# expansion_module_microSD.net
KiCad netlist of a schematic drawn in EAGLE
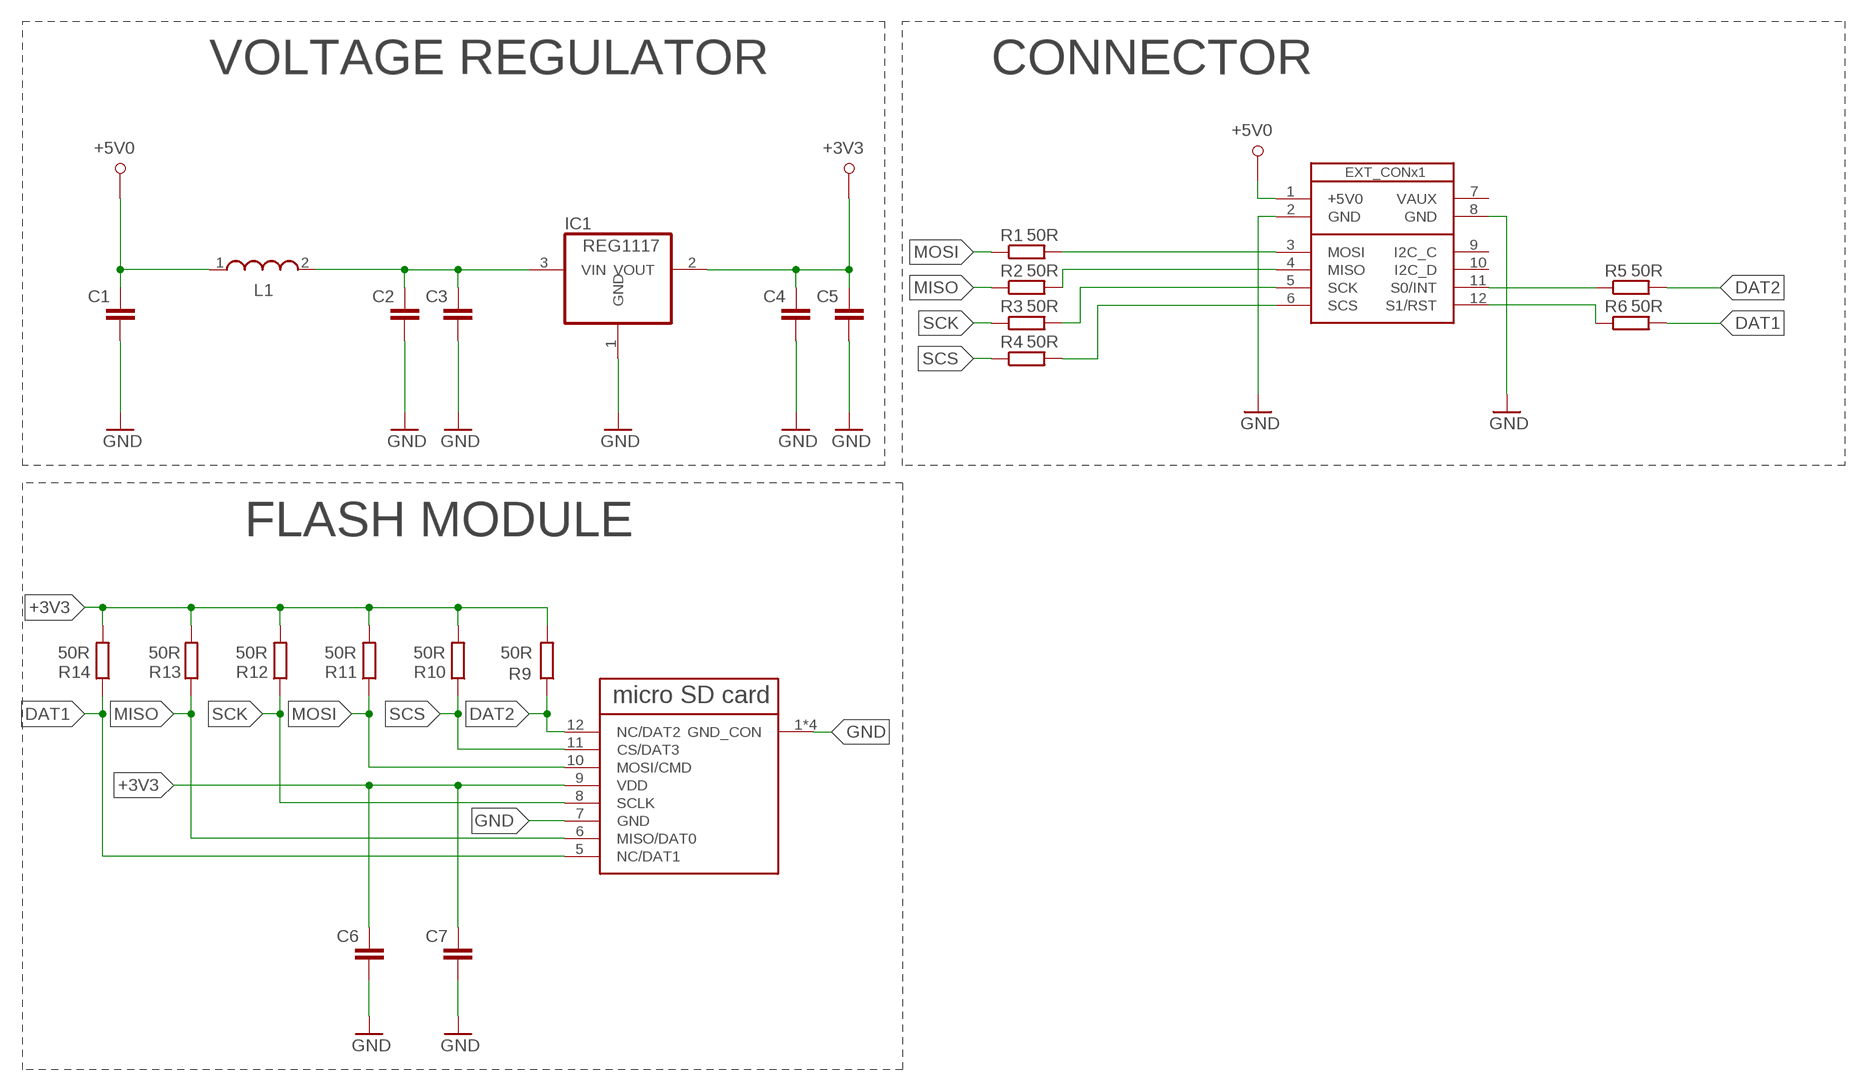
[diagram p0: schematic, sheet 1]

(export (version "E")
  (design (tool "Eeschema 10.0.6"))
  (components
    (comp (ref "C1")
      (value "C-EUC0805")
      (footprint "eagle-import:C0805")
      (libsource (lib "eagle-import") (part "C-EUC0805"))
    )
    (comp (ref "C2")
      (value "C-EUC0805")
      (footprint "eagle-import:C0805")
      (libsource (lib "eagle-import") (part "C-EUC0805"))
    )
    (comp (ref "C3")
      (value "C-EUC0805")
      (footprint "eagle-import:C0805")
      (libsource (lib "eagle-import") (part "C-EUC0805"))
    )
    (comp (ref "C4")
      (value "C-EUC0805")
      (footprint "eagle-import:C0805")
      (libsource (lib "eagle-import") (part "C-EUC0805"))
    )
    (comp (ref "C5")
      (value "C-EUC0805")
      (footprint "eagle-import:C0805")
      (libsource (lib "eagle-import") (part "C-EUC0805"))
    )
    (comp (ref "C6")
      (value "C-EUC0805")
      (footprint "eagle-import:C0805")
      (libsource (lib "eagle-import") (part "C-EUC0805"))
    )
    (comp (ref "C7")
      (value "C-EUC0805")
      (footprint "eagle-import:C0805")
      (libsource (lib "eagle-import") (part "C-EUC0805"))
    )
    (comp (ref "IC1")
      (value "REG1117")
      (footprint "eagle-import:SOT223")
      (libsource (lib "eagle-import") (part "REG1117"))
    )
    (comp (ref "L1")
      (value "WE-LQ_1210")
      (footprint "eagle-import:WE-LQ_M")
      (libsource (lib "eagle-import") (part "WE-LQ_1210"))
    )
    (comp (ref "MICRO_SD_CARD")
      (value "MX5009010801")
      (footprint "eagle-import:MX5009010801")
      (libsource (lib "eagle-import") (part "MX5009010801"))
    )
    (comp (ref "R1")
      (value "50R")
      (footprint "eagle-import:R0805")
      (libsource (lib "eagle-import") (part "R-EU_R0805"))
    )
    (comp (ref "R2")
      (value "50R")
      (footprint "eagle-import:R0805")
      (libsource (lib "eagle-import") (part "R-EU_R0805"))
    )
    (comp (ref "R3")
      (value "50R")
      (footprint "eagle-import:R0805")
      (libsource (lib "eagle-import") (part "R-EU_R0805"))
    )
    (comp (ref "R4")
      (value "50R")
      (footprint "eagle-import:R0805")
      (libsource (lib "eagle-import") (part "R-EU_R0805"))
    )
    (comp (ref "R5")
      (value "50R")
      (footprint "eagle-import:R0805")
      (libsource (lib "eagle-import") (part "R-EU_R0805"))
    )
    (comp (ref "R6")
      (value "50R")
      (footprint "eagle-import:R0805")
      (libsource (lib "eagle-import") (part "R-EU_R0805"))
    )
    (comp (ref "R9")
      (value "50R")
      (footprint "eagle-import:R0805")
      (libsource (lib "eagle-import") (part "R-EU_R0805"))
    )
    (comp (ref "R10")
      (value "50R")
      (footprint "eagle-import:R0805")
      (libsource (lib "eagle-import") (part "R-EU_R0805"))
    )
    (comp (ref "R11")
      (value "50R")
      (footprint "eagle-import:R0805")
      (libsource (lib "eagle-import") (part "R-EU_R0805"))
    )
    (comp (ref "R12")
      (value "50R")
      (footprint "eagle-import:R0805")
      (libsource (lib "eagle-import") (part "R-EU_R0805"))
    )
    (comp (ref "R13")
      (value "50R")
      (footprint "eagle-import:R0805")
      (libsource (lib "eagle-import") (part "R-EU_R0805"))
    )
    (comp (ref "R14")
      (value "50R")
      (footprint "eagle-import:R0805")
      (libsource (lib "eagle-import") (part "R-EU_R0805"))
    )
    (comp (ref "U$1")
      (value "SB_EXT_CON_X1_SPI")
      (footprint "eagle-import:SB_EXT_CON_X1_FULL")
      (libsource (lib "eagle-import") (part "SB_EXT_CON_X1_SPI"))
    )
  )
  (nets
    (net (code "1") (name "+3V3") (class "Default")
      (node (ref "C4") (pin "2") (pinfunction "2_2") (pintype "passive"))
      (node (ref "C5") (pin "2") (pinfunction "2_2") (pintype "passive"))
      (node (ref "C6") (pin "2") (pinfunction "2_2") (pintype "passive"))
      (node (ref "C7") (pin "2") (pinfunction "2_2") (pintype "passive"))
      (node (ref "IC1") (pin "2") (pinfunction "VOUT_2") (pintype "output"))
      (node (ref "MICRO_SD_CARD") (pin "9") (pinfunction "VDD_9") (pintype "bidirectional"))
      (node (ref "R10") (pin "2") (pinfunction "2_2") (pintype "passive"))
      (node (ref "R11") (pin "2") (pinfunction "2_2") (pintype "passive"))
      (node (ref "R12") (pin "2") (pinfunction "2_2") (pintype "passive"))
      (node (ref "R13") (pin "2") (pinfunction "2_2") (pintype "passive"))
      (node (ref "R14") (pin "2") (pinfunction "2_2") (pintype "passive"))
      (node (ref "R9") (pin "2") (pinfunction "2_2") (pintype "passive"))
    )
    (net (code "2") (name "+5V0") (class "Default")
      (node (ref "C1") (pin "2") (pinfunction "2_2") (pintype "passive"))
      (node (ref "L1") (pin "1") (pinfunction "1_1") (pintype "passive"))
      (node (ref "U$1") (pin "1") (pinfunction "+5V0_1") (pintype "bidirectional"))
    )
    (net (code "3") (name "DAT1") (class "Default")
      (node (ref "MICRO_SD_CARD") (pin "5") (pinfunction "NC/DAT1_5") (pintype "bidirectional"))
      (node (ref "R14") (pin "1") (pinfunction "1_1") (pintype "passive"))
      (node (ref "R6") (pin "2") (pinfunction "2_2") (pintype "passive"))
    )
    (net (code "4") (name "DAT2") (class "Default")
      (node (ref "MICRO_SD_CARD") (pin "12") (pinfunction "NC/DAT2_12") (pintype "bidirectional"))
      (node (ref "R5") (pin "2") (pinfunction "2_2") (pintype "passive"))
      (node (ref "R9") (pin "1") (pinfunction "1_1") (pintype "passive"))
    )
    (net (code "5") (name "GND") (class "Default")
      (node (ref "C1") (pin "1") (pinfunction "1_1") (pintype "passive"))
      (node (ref "C2") (pin "1") (pinfunction "1_1") (pintype "passive"))
      (node (ref "C3") (pin "1") (pinfunction "1_1") (pintype "passive"))
      (node (ref "C4") (pin "1") (pinfunction "1_1") (pintype "passive"))
      (node (ref "C5") (pin "1") (pinfunction "1_1") (pintype "passive"))
      (node (ref "C6") (pin "1") (pinfunction "1_1") (pintype "passive"))
      (node (ref "C7") (pin "1") (pinfunction "1_1") (pintype "passive"))
      (node (ref "IC1") (pin "1") (pinfunction "GND_1") (pintype "power_in"))
      (node (ref "MICRO_SD_CARD") (pin "1") (pinfunction "GND_CON_1") (pintype "bidirectional"))
      (node (ref "MICRO_SD_CARD") (pin "2") (pinfunction "GND_CON_2") (pintype "bidirectional"))
      (node (ref "MICRO_SD_CARD") (pin "3") (pinfunction "GND_CON_3") (pintype "bidirectional"))
      (node (ref "MICRO_SD_CARD") (pin "4") (pinfunction "GND_CON_4") (pintype "bidirectional"))
      (node (ref "MICRO_SD_CARD") (pin "7") (pinfunction "GND_7") (pintype "bidirectional"))
      (node (ref "U$1") (pin "2") (pinfunction "GND_2") (pintype "bidirectional"))
      (node (ref "U$1") (pin "8") (pinfunction "GND_8") (pintype "bidirectional"))
    )
    (net (code "6") (name "MISO") (class "Default")
      (node (ref "MICRO_SD_CARD") (pin "6") (pinfunction "MISO/DAT0_6") (pintype "bidirectional"))
      (node (ref "R13") (pin "1") (pinfunction "1_1") (pintype "passive"))
      (node (ref "R2") (pin "1") (pinfunction "1_1") (pintype "passive"))
    )
    (net (code "7") (name "MOSI") (class "Default")
      (node (ref "MICRO_SD_CARD") (pin "10") (pinfunction "MOSI/CMD_10") (pintype "bidirectional"))
      (node (ref "R1") (pin "1") (pinfunction "1_1") (pintype "passive"))
      (node (ref "R11") (pin "1") (pinfunction "1_1") (pintype "passive"))
    )
    (net (code "8") (name "Net-(IC1-VIN)") (class "Default")
      (node (ref "C2") (pin "2") (pinfunction "2_2") (pintype "passive"))
      (node (ref "C3") (pin "2") (pinfunction "2_2") (pintype "passive"))
      (node (ref "IC1") (pin "3") (pinfunction "VIN_3") (pintype "input"))
      (node (ref "L1") (pin "2") (pinfunction "2_2") (pintype "passive"))
    )
    (net (code "9") (name "Net-(U$1-MISO)") (class "Default")
      (node (ref "R2") (pin "2") (pinfunction "2_2") (pintype "passive"))
      (node (ref "U$1") (pin "4") (pinfunction "MISO_4") (pintype "bidirectional"))
    )
    (net (code "10") (name "Net-(U$1-MOSI)") (class "Default")
      (node (ref "R1") (pin "2") (pinfunction "2_2") (pintype "passive"))
      (node (ref "U$1") (pin "3") (pinfunction "MOSI_3") (pintype "bidirectional"))
    )
    (net (code "11") (name "Net-(U$1-S0{slash}INT)") (class "Default")
      (node (ref "R5") (pin "1") (pinfunction "1_1") (pintype "passive"))
      (node (ref "U$1") (pin "11") (pinfunction "S0/INT_11") (pintype "bidirectional"))
    )
    (net (code "12") (name "Net-(U$1-S1{slash}RST)") (class "Default")
      (node (ref "R6") (pin "1") (pinfunction "1_1") (pintype "passive"))
      (node (ref "U$1") (pin "12") (pinfunction "S1/RST_12") (pintype "bidirectional"))
    )
    (net (code "13") (name "Net-(U$1-SCK)") (class "Default")
      (node (ref "R3") (pin "2") (pinfunction "2_2") (pintype "passive"))
      (node (ref "U$1") (pin "5") (pinfunction "SCK_5") (pintype "bidirectional"))
    )
    (net (code "14") (name "Net-(U$1-SCS)") (class "Default")
      (node (ref "R4") (pin "2") (pinfunction "2_2") (pintype "passive"))
      (node (ref "U$1") (pin "6") (pinfunction "SCS_6") (pintype "bidirectional"))
    )
    (net (code "15") (name "SCK") (class "Default")
      (node (ref "MICRO_SD_CARD") (pin "8") (pinfunction "SCLK_8") (pintype "bidirectional"))
      (node (ref "R12") (pin "1") (pinfunction "1_1") (pintype "passive"))
      (node (ref "R3") (pin "1") (pinfunction "1_1") (pintype "passive"))
    )
    (net (code "16") (name "SCS") (class "Default")
      (node (ref "MICRO_SD_CARD") (pin "11") (pinfunction "CS/DAT3_11") (pintype "bidirectional"))
      (node (ref "R10") (pin "1") (pinfunction "1_1") (pintype "passive"))
      (node (ref "R4") (pin "1") (pinfunction "1_1") (pintype "passive"))
    )
    (net (code "17") (name "unconnected-(U$1-I2C_C-Pad9)") (class "Default")
      (node (ref "U$1") (pin "9") (pinfunction "I2C_C_9") (pintype "bidirectional"))
    )
    (net (code "18") (name "unconnected-(U$1-I2C_D-Pad10)") (class "Default")
      (node (ref "U$1") (pin "10") (pinfunction "I2C_D_10") (pintype "bidirectional"))
    )
    (net (code "19") (name "unconnected-(U$1-VAUX-Pad7)") (class "Default")
      (node (ref "U$1") (pin "7") (pinfunction "VAUX_7") (pintype "bidirectional"))
    )
  )
)
